# RailDriver.net
KiCad netlist of a schematic drawn in EAGLE
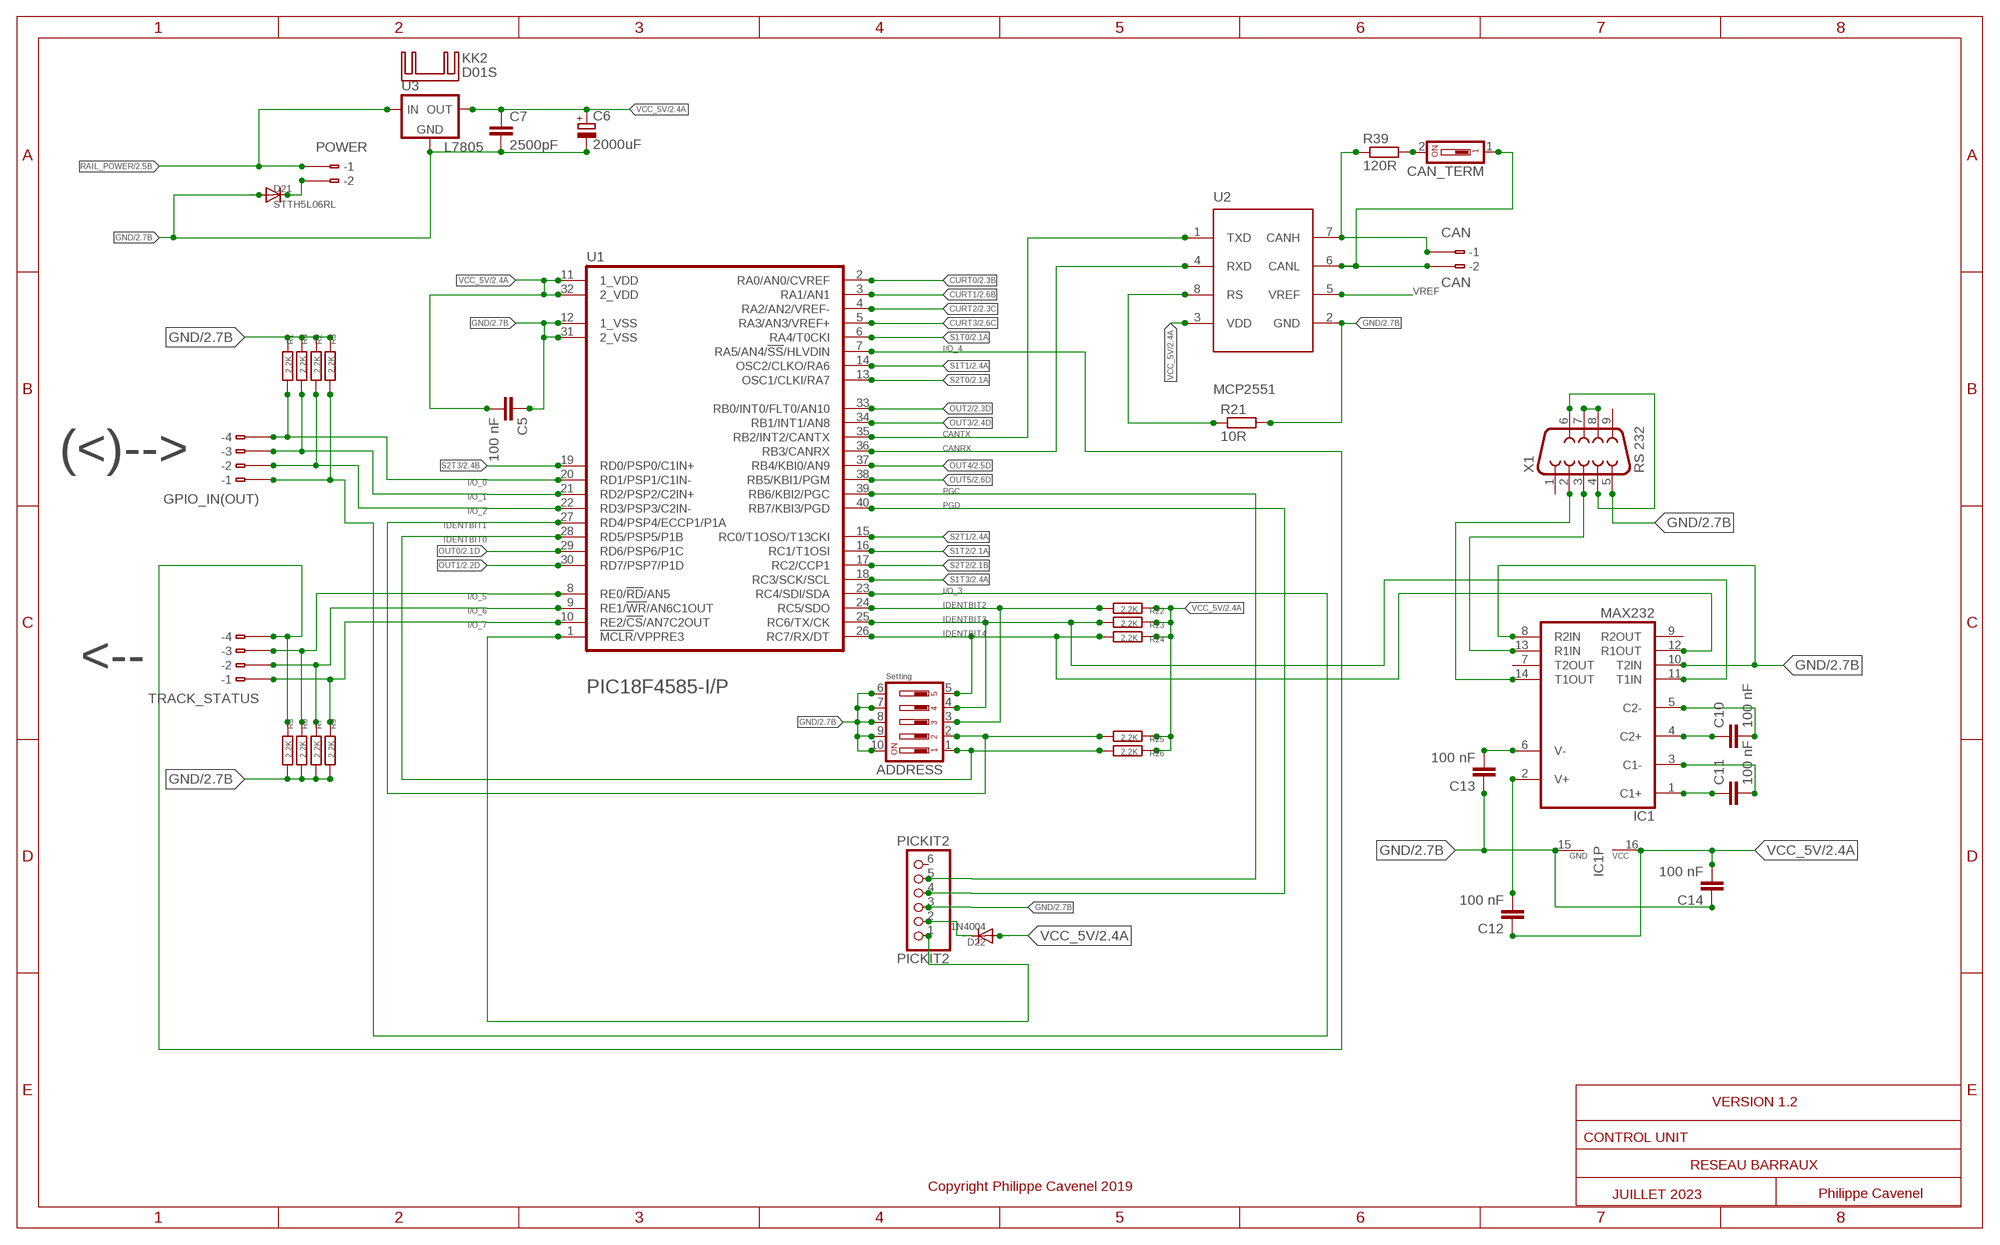
[diagram p0: schematic, sheet 1]
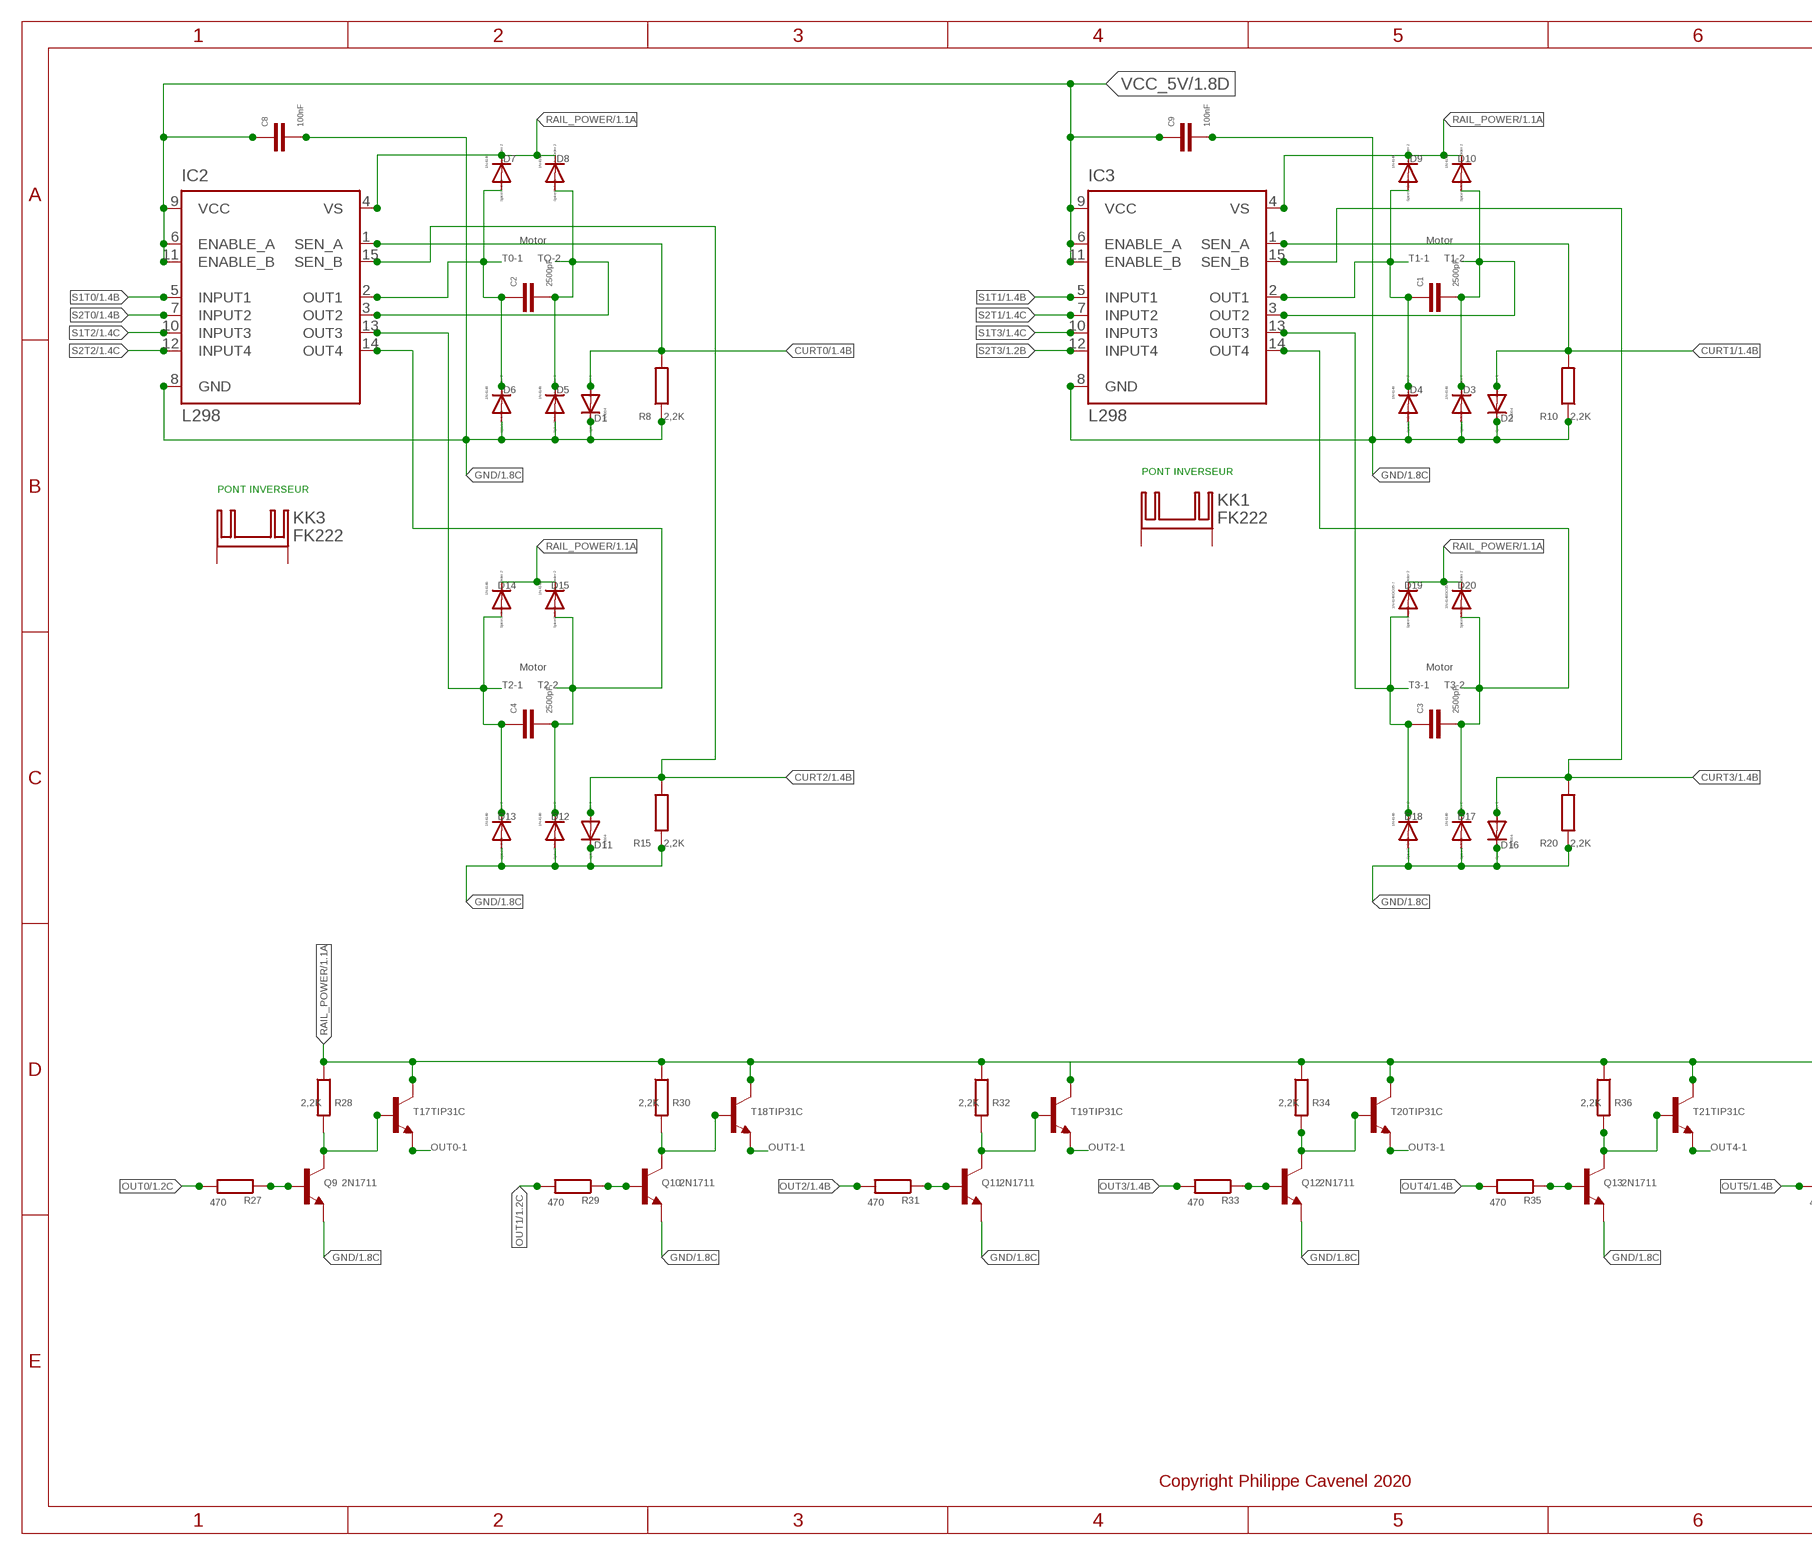
[diagram p1: schematic, sheet 2, part 1 of 2]
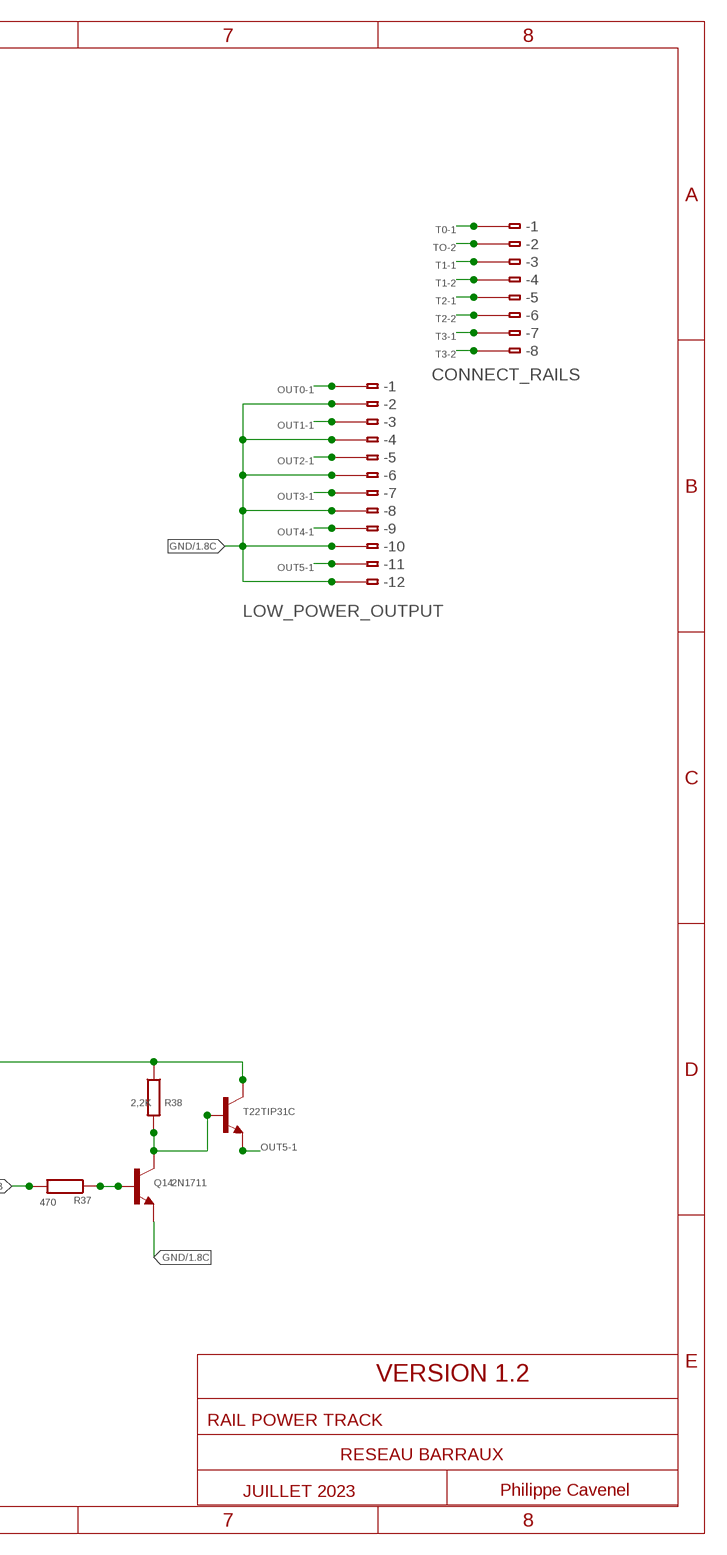
[diagram p2: schematic, sheet 2, part 2 of 2]

(export (version "E")
  (design (tool "Eeschema 10.0.6"))
  (components
    (comp (ref "ADDRESS")
      (value "DIP05YL")
      (footprint "eagle-import:DIP05YL")
      (libsource (lib "eagle-import") (part "DIP05YL"))
    )
    (comp (ref "C5")
      (value "100 nF")
      (footprint "eagle-import:C050-024X044")
      (libsource (lib "eagle-import") (part "C-EU050-024X044"))
    )
    (comp (ref "C6")
      (value "2000uF")
      (footprint "eagle-import:E3,5-10")
      (libsource (lib "eagle-import") (part "CPOL-EUE3.5-10"))
    )
    (comp (ref "C7")
      (value "2500pF")
      (footprint "eagle-import:C050-024X044")
      (libsource (lib "eagle-import") (part "C-EU050-024X044"))
    )
    (comp (ref "C10")
      (value "100 nF")
      (footprint "eagle-import:C050-024X044")
      (libsource (lib "eagle-import") (part "C-EU050-024X044"))
    )
    (comp (ref "C11")
      (value "100 nF")
      (footprint "eagle-import:C050-024X044")
      (libsource (lib "eagle-import") (part "C-EU050-024X044"))
    )
    (comp (ref "C12")
      (value "100 nF")
      (footprint "eagle-import:C050-024X044")
      (libsource (lib "eagle-import") (part "C-EU050-024X044"))
    )
    (comp (ref "C13")
      (value "100 nF")
      (footprint "eagle-import:C050-024X044")
      (libsource (lib "eagle-import") (part "C-EU050-024X044"))
    )
    (comp (ref "C14")
      (value "100 nF")
      (footprint "eagle-import:C050-024X044")
      (libsource (lib "eagle-import") (part "C-EU050-024X044"))
    )
    (comp (ref "CAN")
      (value "CAN")
      (footprint "eagle-import:233-502")
      (fields (field (name "MPN") "233-502"))
      (libsource (lib "eagle-import") (part "233-502"))
    )
    (comp (ref "CAN_TERM")
      (value "DS01")
      (footprint "eagle-import:DS-01")
      (libsource (lib "eagle-import") (part "DS01"))
    )
    (comp (ref "D21")
      (value "STTH5L06RL")
      (footprint "eagle-import:DO201-15")
      (libsource (lib "eagle-import") (part "1N5400"))
    )
    (comp (ref "D22")
      (value "1N4004")
      (footprint "eagle-import:DO41-10")
      (libsource (lib "eagle-import") (part "1N4004"))
    )
    (comp (ref "GPIO_IN(OUT)")
      (value "233-504")
      (footprint "eagle-import:233-504")
      (fields (field (name "MF") "Wago Corporation") (field (name "MPN") "0233-0504"))
      (libsource (lib "eagle-import") (part "233-504"))
    )
    (comp (ref "IC1")
      (value "MAX232")
      (footprint "eagle-import:DIL16")
      (fields (field (name "MF") "MAXIM") (field (name "MPN") "MAX232ACPE+"))
      (libsource (lib "eagle-import") (part "MAX232"))
    )
    (comp (ref "KK2")
      (value "D01S")
      (footprint "eagle-import:D01S")
      (libsource (lib "eagle-import") (part "D01S"))
    )
    (comp (ref "PICKIT2")
      (value "PICKIT2")
      (footprint "eagle-import:1X06")
      (libsource (lib "eagle-import") (part "PINHD-1X6"))
    )
    (comp (ref "POWER")
      (value "233-502")
      (footprint "eagle-import:233-502")
      (libsource (lib "eagle-import") (part "233-502"))
    )
    (comp (ref "R1")
      (value "2,2K")
      (footprint "eagle-import:0204_7")
      (libsource (lib "eagle-import") (part "resistor_R-EU_0204/7"))
    )
    (comp (ref "R2")
      (value "2,2K")
      (footprint "eagle-import:0204_7")
      (libsource (lib "eagle-import") (part "resistor_R-EU_0204/7"))
    )
    (comp (ref "R3")
      (value "2,2K")
      (footprint "eagle-import:0204_7")
      (libsource (lib "eagle-import") (part "resistor_R-EU_0204/7"))
    )
    (comp (ref "R4")
      (value "2,2K")
      (footprint "eagle-import:0204_7")
      (libsource (lib "eagle-import") (part "resistor_R-EU_0204/7"))
    )
    (comp (ref "R5")
      (value "2,2K")
      (footprint "eagle-import:0204_7")
      (libsource (lib "eagle-import") (part "resistor_R-EU_0204/7"))
    )
    (comp (ref "R6")
      (value "2,2K")
      (footprint "eagle-import:0204_7")
      (libsource (lib "eagle-import") (part "resistor_R-EU_0204/7"))
    )
    (comp (ref "R7")
      (value "2,2K")
      (footprint "eagle-import:0204_7")
      (libsource (lib "eagle-import") (part "resistor_R-EU_0204/7"))
    )
    (comp (ref "R9")
      (value "2,2K")
      (footprint "eagle-import:0204_7")
      (libsource (lib "eagle-import") (part "resistor_R-EU_0204/7"))
    )
    (comp (ref "R21")
      (value "10R")
      (footprint "eagle-import:0204_7")
      (libsource (lib "eagle-import") (part "resistor_R-EU_0204/7"))
    )
    (comp (ref "R22")
      (value "2,2K")
      (footprint "eagle-import:0204_7")
      (libsource (lib "eagle-import") (part "resistor_R-EU_0204/7"))
    )
    (comp (ref "R23")
      (value "2,2K")
      (footprint "eagle-import:0204_7")
      (libsource (lib "eagle-import") (part "resistor_R-EU_0204/7"))
    )
    (comp (ref "R24")
      (value "2,2K")
      (footprint "eagle-import:0204_7")
      (libsource (lib "eagle-import") (part "resistor_R-EU_0204/7"))
    )
    (comp (ref "R25")
      (value "2,2K")
      (footprint "eagle-import:0204_7")
      (libsource (lib "eagle-import") (part "resistor_R-EU_0204/7"))
    )
    (comp (ref "R26")
      (value "2,2K")
      (footprint "eagle-import:0204_7")
      (libsource (lib "eagle-import") (part "resistor_R-EU_0204/7"))
    )
    (comp (ref "R39")
      (value "120R")
      (footprint "eagle-import:0204_7")
      (libsource (lib "eagle-import") (part "resistor_R-EU_0204/7"))
    )
    (comp (ref "TRACK_STATUS")
      (value "233-504")
      (footprint "eagle-import:233-504")
      (fields (field (name "MF") "Wago Corporation") (field (name "MPN") "0233-0504"))
      (libsource (lib "eagle-import") (part "233-504"))
    )
    (comp (ref "U1")
      (value "PIC18F4585-I")
      (footprint "eagle-import:DIL_SOCKET40W")
      (fields (field (name "MF") "Microchip") (field (name "MPN") "PIC18F4585-I/P"))
      (libsource (lib "eagle-import") (part "MICROCHIP_PIC18F4585-I-PDIL_SOCKET40W"))
    )
    (comp (ref "U2")
      (value "MCP2551")
      (footprint "eagle-import:DIL_SOCKET8")
      (libsource (lib "eagle-import") (part "MCP2551P"))
    )
    (comp (ref "U3")
      (value "L7805")
      (footprint "eagle-import:TO220BV")
      (libsource (lib "eagle-import") (part "78XX-TO220V"))
    )
    (comp (ref "X1")
      (value "RS 232")
      (footprint "eagle-import:F09HP")
      (libsource (lib "eagle-import") (part "F09HP"))
    )
    (comp (ref "C1")
      (value "2500pF")
      (footprint "eagle-import:C050-024X044")
      (libsource (lib "eagle-import") (part "C-EU050-024X044"))
    )
    (comp (ref "C2")
      (value "2500pF")
      (footprint "eagle-import:C050-024X044")
      (libsource (lib "eagle-import") (part "C-EU050-024X044"))
    )
    (comp (ref "C3")
      (value "2500pF")
      (footprint "eagle-import:C050-024X044")
      (libsource (lib "eagle-import") (part "C-EU050-024X044"))
    )
    (comp (ref "C4")
      (value "2500pF")
      (footprint "eagle-import:C050-024X044")
      (libsource (lib "eagle-import") (part "C-EU050-024X044"))
    )
    (comp (ref "C8")
      (value "100nF")
      (footprint "eagle-import:C050-024X044")
      (libsource (lib "eagle-import") (part "C-EU050-024X044"))
    )
    (comp (ref "C9")
      (value "100nF")
      (footprint "eagle-import:C050-024X044")
      (libsource (lib "eagle-import") (part "C-EU050-024X044"))
    )
    (comp (ref "CONNECT_RAILS")
      (value "233-508")
      (footprint "eagle-import:233-508")
      (fields (field (name "MF") "Wago Corporation") (field (name "MPN") "0233-0508"))
      (libsource (lib "eagle-import") (part "233-508"))
    )
    (comp (ref "D1")
      (value "1N4004")
      (footprint "eagle-import:DO41-10")
      (libsource (lib "eagle-import") (part "1N4004"))
    )
    (comp (ref "D2")
      (value "1N4004")
      (footprint "eagle-import:DO41-10")
      (libsource (lib "eagle-import") (part "1N4004"))
    )
    (comp (ref "D3")
      (value "1N4148")
      (footprint "eagle-import:DO35-7")
      (libsource (lib "eagle-import") (part "1N4148DO35-7"))
    )
    (comp (ref "D4")
      (value "1N4148")
      (footprint "eagle-import:DO35-7")
      (libsource (lib "eagle-import") (part "1N4148DO35-7"))
    )
    (comp (ref "D5")
      (value "1N4148")
      (footprint "eagle-import:DO35-7")
      (libsource (lib "eagle-import") (part "1N4148DO35-7"))
    )
    (comp (ref "D6")
      (value "1N4148")
      (footprint "eagle-import:DO35-7")
      (libsource (lib "eagle-import") (part "1N4148DO35-7"))
    )
    (comp (ref "D7")
      (value "1N4148")
      (footprint "eagle-import:DO35-7")
      (libsource (lib "eagle-import") (part "1N4148DO35-7"))
    )
    (comp (ref "D8")
      (value "1N4148")
      (footprint "eagle-import:DO35-7")
      (libsource (lib "eagle-import") (part "1N4148DO35-7"))
    )
    (comp (ref "D9")
      (value "1N4148")
      (footprint "eagle-import:DO35-7")
      (libsource (lib "eagle-import") (part "1N4148DO35-7"))
    )
    (comp (ref "D10")
      (value "1N4148")
      (footprint "eagle-import:DO35-7")
      (libsource (lib "eagle-import") (part "1N4148DO35-7"))
    )
    (comp (ref "D11")
      (value "1N4004")
      (footprint "eagle-import:DO41-10")
      (libsource (lib "eagle-import") (part "1N4004"))
    )
    (comp (ref "D12")
      (value "1N4148")
      (footprint "eagle-import:DO35-7")
      (libsource (lib "eagle-import") (part "1N4148DO35-7"))
    )
    (comp (ref "D13")
      (value "1N4148")
      (footprint "eagle-import:DO35-7")
      (libsource (lib "eagle-import") (part "1N4148DO35-7"))
    )
    (comp (ref "D14")
      (value "1N4148")
      (footprint "eagle-import:DO35-7")
      (libsource (lib "eagle-import") (part "1N4148DO35-7"))
    )
    (comp (ref "D15")
      (value "1N4148")
      (footprint "eagle-import:DO35-7")
      (libsource (lib "eagle-import") (part "1N4148DO35-7"))
    )
    (comp (ref "D16")
      (value "1N4004")
      (footprint "eagle-import:DO41-10")
      (libsource (lib "eagle-import") (part "1N4004"))
    )
    (comp (ref "D17")
      (value "1N4148")
      (footprint "eagle-import:DO35-7")
      (libsource (lib "eagle-import") (part "1N4148DO35-7"))
    )
    (comp (ref "D18")
      (value "1N4148")
      (footprint "eagle-import:DO35-7")
      (libsource (lib "eagle-import") (part "1N4148DO35-7"))
    )
    (comp (ref "D19")
      (value "1N4148DO35-7")
      (footprint "eagle-import:DO35-7")
      (libsource (lib "eagle-import") (part "1N4148DO35-7"))
    )
    (comp (ref "D20")
      (value "1N4148DO35-7")
      (footprint "eagle-import:DO35-7")
      (libsource (lib "eagle-import") (part "1N4148DO35-7"))
    )
    (comp (ref "IC2")
      (value "L298")
      (footprint "eagle-import:MULTIWATT-15")
      (fields (field (name "MPN") "L298N"))
      (libsource (lib "eagle-import") (part "L298"))
    )
    (comp (ref "IC3")
      (value "L298")
      (footprint "eagle-import:MULTIWATT-15")
      (fields (field (name "MPN") "L298N"))
      (libsource (lib "eagle-import") (part "L298"))
    )
    (comp (ref "KK1")
      (value "FK222")
      (footprint "eagle-import:FK222")
      (libsource (lib "eagle-import") (part "FK222"))
    )
    (comp (ref "KK3")
      (value "FK222")
      (footprint "eagle-import:FK222")
      (libsource (lib "eagle-import") (part "FK222"))
    )
    (comp (ref "LOW_POWER_OUTPUT")
      (value "233-512")
      (footprint "eagle-import:233-512")
      (fields (field (name "MF") "Wago Corporation") (field (name "MPN") "0233-0512"))
      (libsource (lib "eagle-import") (part "233-512"))
    )
    (comp (ref "Q9")
      (value "2N1711")
      (footprint "eagle-import:TO39")
      (libsource (lib "eagle-import") (part "2N1711"))
    )
    (comp (ref "Q10")
      (value "2N1711")
      (footprint "eagle-import:TO39")
      (libsource (lib "eagle-import") (part "2N1711"))
    )
    (comp (ref "Q11")
      (value "2N1711")
      (footprint "eagle-import:TO39")
      (libsource (lib "eagle-import") (part "2N1711"))
    )
    (comp (ref "Q12")
      (value "2N1711")
      (footprint "eagle-import:TO39")
      (libsource (lib "eagle-import") (part "2N1711"))
    )
    (comp (ref "Q13")
      (value "2N1711")
      (footprint "eagle-import:TO39")
      (libsource (lib "eagle-import") (part "2N1711"))
    )
    (comp (ref "Q14")
      (value "2N1711")
      (footprint "eagle-import:TO39")
      (libsource (lib "eagle-import") (part "2N1711"))
    )
    (comp (ref "R8")
      (value "2,2K")
      (footprint "eagle-import:0204_7")
      (libsource (lib "eagle-import") (part "R-EU_0204/7"))
    )
    (comp (ref "R10")
      (value "2,2K")
      (footprint "eagle-import:0204_7")
      (libsource (lib "eagle-import") (part "R-EU_0204/7"))
    )
    (comp (ref "R15")
      (value "2,2K")
      (footprint "eagle-import:0204_7")
      (libsource (lib "eagle-import") (part "R-EU_0204/7"))
    )
    (comp (ref "R20")
      (value "2,2K")
      (footprint "eagle-import:0204_7")
      (libsource (lib "eagle-import") (part "R-EU_0204/7"))
    )
    (comp (ref "R27")
      (value "470")
      (footprint "eagle-import:0204_7")
      (libsource (lib "eagle-import") (part "R-EU_0204/7"))
    )
    (comp (ref "R28")
      (value "2,2K")
      (footprint "eagle-import:0204_7")
      (libsource (lib "eagle-import") (part "R-EU_0204/7"))
    )
    (comp (ref "R29")
      (value "470")
      (footprint "eagle-import:0204_7")
      (libsource (lib "eagle-import") (part "R-EU_0204/7"))
    )
    (comp (ref "R30")
      (value "2,2K")
      (footprint "eagle-import:0204_7")
      (libsource (lib "eagle-import") (part "R-EU_0204/7"))
    )
    (comp (ref "R31")
      (value "470")
      (footprint "eagle-import:0204_7")
      (libsource (lib "eagle-import") (part "R-EU_0204/7"))
    )
    (comp (ref "R32")
      (value "2,2K")
      (footprint "eagle-import:0204_7")
      (libsource (lib "eagle-import") (part "R-EU_0204/7"))
    )
    (comp (ref "R33")
      (value "470")
      (footprint "eagle-import:0204_7")
      (libsource (lib "eagle-import") (part "R-EU_0204/7"))
    )
    (comp (ref "R34")
      (value "2,2K")
      (footprint "eagle-import:0204_7")
      (libsource (lib "eagle-import") (part "R-EU_0204/7"))
    )
    (comp (ref "R35")
      (value "470")
      (footprint "eagle-import:0204_7")
      (libsource (lib "eagle-import") (part "R-EU_0204/7"))
    )
    (comp (ref "R36")
      (value "2,2K")
      (footprint "eagle-import:0204_7")
      (libsource (lib "eagle-import") (part "R-EU_0204/7"))
    )
    (comp (ref "R37")
      (value "470")
      (footprint "eagle-import:0204_7")
      (libsource (lib "eagle-import") (part "R-EU_0204/7"))
    )
    (comp (ref "R38")
      (value "2,2K")
      (footprint "eagle-import:0204_7")
      (libsource (lib "eagle-import") (part "R-EU_0204/7"))
    )
    (comp (ref "T17")
      (value "TIP31C")
      (footprint "eagle-import:TO220")
      (libsource (lib "eagle-import") (part "TIP31C"))
    )
    (comp (ref "T18")
      (value "TIP31C")
      (footprint "eagle-import:TO220")
      (libsource (lib "eagle-import") (part "TIP31C"))
    )
    (comp (ref "T19")
      (value "TIP31C")
      (footprint "eagle-import:TO220")
      (libsource (lib "eagle-import") (part "TIP31C"))
    )
    (comp (ref "T20")
      (value "TIP31C")
      (footprint "eagle-import:TO220")
      (libsource (lib "eagle-import") (part "TIP31C"))
    )
    (comp (ref "T21")
      (value "TIP31C")
      (footprint "eagle-import:TO220")
      (libsource (lib "eagle-import") (part "TIP31C"))
    )
    (comp (ref "T22")
      (value "TIP31C")
      (footprint "eagle-import:TO220")
      (libsource (lib "eagle-import") (part "TIP31C"))
    )
  )
  (nets
    (net (code "1") (name "CANRX") (class "Default")
      (node (ref "U1") (pin "36") (pinfunction "RB3/CANRX_36") (pintype "bidirectional"))
      (node (ref "U2") (pin "4") (pinfunction "RXD_4") (pintype "output"))
    )
    (net (code "2") (name "CANTX") (class "Default")
      (node (ref "U1") (pin "35") (pinfunction "RB2/INT2/CANTX_35") (pintype "bidirectional"))
      (node (ref "U2") (pin "1") (pinfunction "TXD_1") (pintype "input"))
    )
    (net (code "3") (name "CURT0") (class "Default")
      (node (ref "D1") (pin "A") (pinfunction "A_A") (pintype "passive"))
      (node (ref "IC2") (pin "1") (pinfunction "SEN_A_1") (pintype "input"))
      (node (ref "R8") (pin "2") (pinfunction "2_2") (pintype "passive"))
      (node (ref "U1") (pin "2") (pinfunction "RA0/AN0/CVREF_2") (pintype "bidirectional"))
    )
    (net (code "4") (name "CURT1") (class "Default")
      (node (ref "D2") (pin "A") (pinfunction "A_A") (pintype "passive"))
      (node (ref "IC3") (pin "1") (pinfunction "SEN_A_1") (pintype "input"))
      (node (ref "R10") (pin "2") (pinfunction "2_2") (pintype "passive"))
      (node (ref "U1") (pin "3") (pinfunction "RA1/AN1_3") (pintype "bidirectional"))
    )
    (net (code "5") (name "CURT2") (class "Default")
      (node (ref "D11") (pin "A") (pinfunction "A_A") (pintype "passive"))
      (node (ref "IC2") (pin "15") (pinfunction "SEN_B_15") (pintype "input"))
      (node (ref "R15") (pin "2") (pinfunction "2_2") (pintype "passive"))
      (node (ref "U1") (pin "4") (pinfunction "RA2/AN2/VREF-_4") (pintype "bidirectional"))
    )
    (net (code "6") (name "CURT3") (class "Default")
      (node (ref "D16") (pin "A") (pinfunction "A_A") (pintype "passive"))
      (node (ref "IC3") (pin "15") (pinfunction "SEN_B_15") (pintype "input"))
      (node (ref "R20") (pin "2") (pinfunction "2_2") (pintype "passive"))
      (node (ref "U1") (pin "5") (pinfunction "RA3/AN3/VREF+_5") (pintype "bidirectional"))
    )
    (net (code "7") (name "GND") (class "Default")
      (node (ref "ADDRESS") (pin "10") (pinfunction "10_10") (pintype "passive"))
      (node (ref "ADDRESS") (pin "6") (pinfunction "6_6") (pintype "passive"))
      (node (ref "ADDRESS") (pin "7") (pinfunction "7_7") (pintype "passive"))
      (node (ref "ADDRESS") (pin "8") (pinfunction "8_8") (pintype "passive"))
      (node (ref "ADDRESS") (pin "9") (pinfunction "9_9") (pintype "passive"))
      (node (ref "C13") (pin "1") (pinfunction "1_1") (pintype "passive"))
      (node (ref "C14") (pin "1") (pinfunction "1_1") (pintype "passive"))
      (node (ref "C5") (pin "1") (pinfunction "1_1") (pintype "passive"))
      (node (ref "C6") (pin "-") (pinfunction "-_-") (pintype "passive"))
      (node (ref "C7") (pin "2") (pinfunction "2_2") (pintype "passive"))
      (node (ref "C8") (pin "2") (pinfunction "2_2") (pintype "passive"))
      (node (ref "C9") (pin "2") (pinfunction "2_2") (pintype "passive"))
      (node (ref "D1") (pin "C") (pinfunction "C_C") (pintype "passive"))
      (node (ref "D11") (pin "C") (pinfunction "C_C") (pintype "passive"))
      (node (ref "D12") (pin "A") (pinfunction "A_A") (pintype "passive"))
      (node (ref "D13") (pin "A") (pinfunction "A_A") (pintype "passive"))
      (node (ref "D16") (pin "C") (pinfunction "C_C") (pintype "passive"))
      (node (ref "D17") (pin "A") (pinfunction "A_A") (pintype "passive"))
      (node (ref "D18") (pin "A") (pinfunction "A_A") (pintype "passive"))
      (node (ref "D2") (pin "C") (pinfunction "C_C") (pintype "passive"))
      (node (ref "D21") (pin "A") (pinfunction "A_A") (pintype "passive"))
      (node (ref "D3") (pin "A") (pinfunction "A_A") (pintype "passive"))
      (node (ref "D4") (pin "A") (pinfunction "A_A") (pintype "passive"))
      (node (ref "D5") (pin "A") (pinfunction "A_A") (pintype "passive"))
      (node (ref "D6") (pin "A") (pinfunction "A_A") (pintype "passive"))
      (node (ref "IC1") (pin "10") (pinfunction "T2IN_10") (pintype "input"))
      (node (ref "IC1") (pin "15") (pinfunction "GND_15") (pintype "power_in"))
      (node (ref "IC1") (pin "8") (pinfunction "R2IN_8") (pintype "input"))
      (node (ref "IC2") (pin "8") (pinfunction "GND_8") (pintype "power_in"))
      (node (ref "IC3") (pin "8") (pinfunction "GND_8") (pintype "power_in"))
      (node (ref "LOW_POWER_OUTPUT") (pin "B10") (pinfunction "B-10_B10") (pintype "passive"))
      (node (ref "LOW_POWER_OUTPUT") (pin "B12") (pinfunction "B-12_B12") (pintype "passive"))
      (node (ref "LOW_POWER_OUTPUT") (pin "B2") (pinfunction "B-2_B2") (pintype "passive"))
      (node (ref "LOW_POWER_OUTPUT") (pin "B4") (pinfunction "B-4_B4") (pintype "passive"))
      (node (ref "LOW_POWER_OUTPUT") (pin "B6") (pinfunction "B-6_B6") (pintype "passive"))
      (node (ref "LOW_POWER_OUTPUT") (pin "B8") (pinfunction "B-8_B8") (pintype "passive"))
      (node (ref "PICKIT2") (pin "3") (pinfunction "3_3") (pintype "passive"))
      (node (ref "Q10") (pin "1") (pinfunction "E_1") (pintype "passive"))
      (node (ref "Q11") (pin "1") (pinfunction "E_1") (pintype "passive"))
      (node (ref "Q12") (pin "1") (pinfunction "E_1") (pintype "passive"))
      (node (ref "Q13") (pin "1") (pinfunction "E_1") (pintype "passive"))
      (node (ref "Q14") (pin "1") (pinfunction "E_1") (pintype "passive"))
      (node (ref "Q9") (pin "1") (pinfunction "E_1") (pintype "passive"))
      (node (ref "R1") (pin "2") (pinfunction "2_2") (pintype "passive"))
      (node (ref "R10") (pin "1") (pinfunction "1_1") (pintype "passive"))
      (node (ref "R15") (pin "1") (pinfunction "1_1") (pintype "passive"))
      (node (ref "R2") (pin "2") (pinfunction "2_2") (pintype "passive"))
      (node (ref "R20") (pin "1") (pinfunction "1_1") (pintype "passive"))
      (node (ref "R21") (pin "2") (pinfunction "2_2") (pintype "passive"))
      (node (ref "R3") (pin "2") (pinfunction "2_2") (pintype "passive"))
      (node (ref "R4") (pin "2") (pinfunction "2_2") (pintype "passive"))
      (node (ref "R5") (pin "1") (pinfunction "1_1") (pintype "passive"))
      (node (ref "R6") (pin "1") (pinfunction "1_1") (pintype "passive"))
      (node (ref "R7") (pin "1") (pinfunction "1_1") (pintype "passive"))
      (node (ref "R8") (pin "1") (pinfunction "1_1") (pintype "passive"))
      (node (ref "R9") (pin "1") (pinfunction "1_1") (pintype "passive"))
      (node (ref "U1") (pin "12") (pinfunction "1_VSS_12") (pintype "power_in"))
      (node (ref "U1") (pin "31") (pinfunction "2_VSS_31") (pintype "power_in"))
      (node (ref "U2") (pin "2") (pinfunction "GND_2") (pintype "power_in"))
      (node (ref "U3") (pin "2") (pinfunction "GND_2") (pintype "power_in"))
      (node (ref "X1") (pin "5") (pinfunction "5_5") (pintype "passive"))
    )
    (net (code "8") (name "IDENTBIT0") (class "Default")
      (node (ref "ADDRESS") (pin "1") (pinfunction "1_1") (pintype "passive"))
      (node (ref "R26") (pin "1") (pinfunction "1_1") (pintype "passive"))
      (node (ref "U1") (pin "28") (pinfunction "RD5/PSP5/P1B_28") (pintype "bidirectional"))
    )
    (net (code "9") (name "IDENTBIT1") (class "Default")
      (node (ref "ADDRESS") (pin "2") (pinfunction "2_2") (pintype "passive"))
      (node (ref "R25") (pin "1") (pinfunction "1_1") (pintype "passive"))
      (node (ref "U1") (pin "27") (pinfunction "RD4/PSP4/ECCP1/P1A_27") (pintype "bidirectional"))
    )
    (net (code "10") (name "IDENTBIT2") (class "Default")
      (node (ref "ADDRESS") (pin "3") (pinfunction "3_3") (pintype "passive"))
      (node (ref "R22") (pin "1") (pinfunction "1_1") (pintype "passive"))
      (node (ref "U1") (pin "24") (pinfunction "RC5/SDO_24") (pintype "bidirectional"))
    )
    (net (code "11") (name "IDENTBIT3") (class "Default")
      (node (ref "ADDRESS") (pin "4") (pinfunction "4_4") (pintype "passive"))
      (node (ref "IC1") (pin "11") (pinfunction "T1IN_11") (pintype "input"))
      (node (ref "R23") (pin "1") (pinfunction "1_1") (pintype "passive"))
      (node (ref "U1") (pin "25") (pinfunction "RC6/TX/CK_25") (pintype "bidirectional"))
    )
    (net (code "12") (name "IDENTBIT4") (class "Default")
      (node (ref "ADDRESS") (pin "5") (pinfunction "5_5") (pintype "passive"))
      (node (ref "IC1") (pin "12") (pinfunction "R1OUT_12") (pintype "output"))
      (node (ref "R24") (pin "1") (pinfunction "1_1") (pintype "passive"))
      (node (ref "U1") (pin "26") (pinfunction "RC7/RX/DT_26") (pintype "bidirectional"))
    )
    (net (code "13") (name "I{slash}O_0") (class "Default")
      (node (ref "GPIO_IN(OUT)") (pin "B4") (pinfunction "B-4_B4") (pintype "passive"))
      (node (ref "R1") (pin "1") (pinfunction "1_1") (pintype "passive"))
      (node (ref "U1") (pin "20") (pinfunction "RD1/PSP1/C1IN-_20") (pintype "bidirectional"))
    )
    (net (code "14") (name "I{slash}O_1") (class "Default")
      (node (ref "GPIO_IN(OUT)") (pin "B3") (pinfunction "B-3_B3") (pintype "passive"))
      (node (ref "R4") (pin "1") (pinfunction "1_1") (pintype "passive"))
      (node (ref "U1") (pin "21") (pinfunction "RD2/PSP2/C2IN+_21") (pintype "bidirectional"))
    )
    (net (code "15") (name "I{slash}O_2") (class "Default")
      (node (ref "GPIO_IN(OUT)") (pin "B2") (pinfunction "B-2_B2") (pintype "passive"))
      (node (ref "R2") (pin "1") (pinfunction "1_1") (pintype "passive"))
      (node (ref "U1") (pin "22") (pinfunction "RD3/PSP3/C2IN-_22") (pintype "bidirectional"))
    )
    (net (code "16") (name "I{slash}O_3") (class "Default")
      (node (ref "GPIO_IN(OUT)") (pin "B1") (pinfunction "B-1_B1") (pintype "passive"))
      (node (ref "R3") (pin "1") (pinfunction "1_1") (pintype "passive"))
      (node (ref "U1") (pin "23") (pinfunction "RC4/SDI/SDA_23") (pintype "bidirectional"))
    )
    (net (code "17") (name "I{slash}O_4") (class "Default")
      (node (ref "R5") (pin "2") (pinfunction "2_2") (pintype "passive"))
      (node (ref "TRACK_STATUS") (pin "B4") (pinfunction "B-4_B4") (pintype "passive"))
      (node (ref "U1") (pin "7") (pinfunction "RA5/AN4/~{SS}/HLVDIN_7") (pintype "bidirectional"))
    )
    (net (code "18") (name "I{slash}O_5") (class "Default")
      (node (ref "R6") (pin "2") (pinfunction "2_2") (pintype "passive"))
      (node (ref "TRACK_STATUS") (pin "B3") (pinfunction "B-3_B3") (pintype "passive"))
      (node (ref "U1") (pin "8") (pinfunction "RE0/~{RD}/AN5_8") (pintype "bidirectional"))
    )
    (net (code "19") (name "I{slash}O_6") (class "Default")
      (node (ref "R7") (pin "2") (pinfunction "2_2") (pintype "passive"))
      (node (ref "TRACK_STATUS") (pin "B2") (pinfunction "B-2_B2") (pintype "passive"))
      (node (ref "U1") (pin "9") (pinfunction "RE1/~{WR}/AN6C1OUT_9") (pintype "bidirectional"))
    )
    (net (code "20") (name "I{slash}O_7") (class "Default")
      (node (ref "R9") (pin "2") (pinfunction "2_2") (pintype "passive"))
      (node (ref "TRACK_STATUS") (pin "B1") (pinfunction "B-1_B1") (pintype "passive"))
      (node (ref "U1") (pin "10") (pinfunction "RE2/~{CS}/AN7C2OUT_10") (pintype "bidirectional"))
    )
    (net (code "21") (name "Net-(CAN-B-1)") (class "Default")
      (node (ref "CAN") (pin "B1") (pinfunction "B-1_B1") (pintype "passive"))
      (node (ref "R39") (pin "1") (pinfunction "1_1") (pintype "passive"))
      (node (ref "U2") (pin "7") (pinfunction "CANH_7") (pintype "bidirectional"))
    )
    (net (code "22") (name "Net-(CAN-B-2)") (class "Default")
      (node (ref "CAN") (pin "B2") (pinfunction "B-2_B2") (pintype "passive"))
      (node (ref "CAN_TERM") (pin "1") (pinfunction "1_1") (pintype "passive"))
      (node (ref "U2") (pin "6") (pinfunction "CANL_6") (pintype "bidirectional"))
    )
    (net (code "23") (name "Net-(CAN_TERM-Pad2)") (class "Default")
      (node (ref "CAN_TERM") (pin "2") (pinfunction "2_2") (pintype "passive"))
      (node (ref "R39") (pin "2") (pinfunction "2_2") (pintype "passive"))
    )
    (net (code "24") (name "Net-(D22-PadC)") (class "Default")
      (node (ref "D22") (pin "C") (pinfunction "C_C") (pintype "passive"))
      (node (ref "PICKIT2") (pin "2") (pinfunction "2_2") (pintype "passive"))
    )
    (net (code "25") (name "Net-(IC1A-C1+)") (class "Default")
      (node (ref "C11") (pin "1") (pinfunction "1_1") (pintype "passive"))
      (node (ref "IC1") (pin "1") (pinfunction "C1+_1") (pintype "bidirectional"))
    )
    (net (code "26") (name "Net-(IC1A-C1-)") (class "Default")
      (node (ref "C11") (pin "2") (pinfunction "2_2") (pintype "passive"))
      (node (ref "IC1") (pin "3") (pinfunction "C1-_3") (pintype "bidirectional"))
    )
    (net (code "27") (name "Net-(IC1A-C2+)") (class "Default")
      (node (ref "C10") (pin "1") (pinfunction "1_1") (pintype "passive"))
      (node (ref "IC1") (pin "4") (pinfunction "C2+_4") (pintype "bidirectional"))
    )
    (net (code "28") (name "Net-(IC1A-C2-)") (class "Default")
      (node (ref "C10") (pin "2") (pinfunction "2_2") (pintype "passive"))
      (node (ref "IC1") (pin "5") (pinfunction "C2-_5") (pintype "bidirectional"))
    )
    (net (code "29") (name "Net-(IC1A-R1IN)") (class "Default")
      (node (ref "IC1") (pin "13") (pinfunction "R1IN_13") (pintype "input"))
      (node (ref "X1") (pin "3") (pinfunction "3_3") (pintype "passive"))
    )
    (net (code "30") (name "Net-(IC1A-T1OUT)") (class "Default")
      (node (ref "IC1") (pin "14") (pinfunction "T1OUT_14") (pintype "output"))
      (node (ref "X1") (pin "2") (pinfunction "2_2") (pintype "passive"))
    )
    (net (code "31") (name "Net-(IC1A-V+)") (class "Default")
      (node (ref "C12") (pin "2") (pinfunction "2_2") (pintype "passive"))
      (node (ref "IC1") (pin "2") (pinfunction "V+_2") (pintype "bidirectional"))
    )
    (net (code "32") (name "Net-(IC1A-V-)") (class "Default")
      (node (ref "C13") (pin "2") (pinfunction "2_2") (pintype "passive"))
      (node (ref "IC1") (pin "6") (pinfunction "V-_6") (pintype "bidirectional"))
    )
    (net (code "33") (name "Net-(POWER-B-2)") (class "Default")
      (node (ref "D21") (pin "C") (pinfunction "C_C") (pintype "passive"))
      (node (ref "POWER") (pin "B2") (pinfunction "B-2_B2") (pintype "passive"))
    )
    (net (code "34") (name "Net-(Q9-B)") (class "Default")
      (node (ref "Q9") (pin "2") (pinfunction "B_2") (pintype "passive"))
      (node (ref "R27") (pin "1") (pinfunction "1_1") (pintype "passive"))
    )
    (net (code "35") (name "Net-(Q9-C)") (class "Default")
      (node (ref "Q9") (pin "3") (pinfunction "C_3") (pintype "passive"))
      (node (ref "R28") (pin "2") (pinfunction "2_2") (pintype "passive"))
      (node (ref "T17") (pin "1") (pinfunction "B_1") (pintype "passive"))
    )
    (net (code "36") (name "Net-(Q10-B)") (class "Default")
      (node (ref "Q10") (pin "2") (pinfunction "B_2") (pintype "passive"))
      (node (ref "R29") (pin "1") (pinfunction "1_1") (pintype "passive"))
    )
    (net (code "37") (name "Net-(Q10-C)") (class "Default")
      (node (ref "Q10") (pin "3") (pinfunction "C_3") (pintype "passive"))
      (node (ref "R30") (pin "2") (pinfunction "2_2") (pintype "passive"))
      (node (ref "T18") (pin "1") (pinfunction "B_1") (pintype "passive"))
    )
    (net (code "38") (name "Net-(Q11-B)") (class "Default")
      (node (ref "Q11") (pin "2") (pinfunction "B_2") (pintype "passive"))
      (node (ref "R31") (pin "1") (pinfunction "1_1") (pintype "passive"))
    )
    (net (code "39") (name "Net-(Q11-C)") (class "Default")
      (node (ref "Q11") (pin "3") (pinfunction "C_3") (pintype "passive"))
      (node (ref "R32") (pin "2") (pinfunction "2_2") (pintype "passive"))
      (node (ref "T19") (pin "1") (pinfunction "B_1") (pintype "passive"))
    )
    (net (code "40") (name "Net-(Q12-B)") (class "Default")
      (node (ref "Q12") (pin "2") (pinfunction "B_2") (pintype "passive"))
      (node (ref "R33") (pin "1") (pinfunction "1_1") (pintype "passive"))
    )
    (net (code "41") (name "Net-(Q12-C)") (class "Default")
      (node (ref "Q12") (pin "3") (pinfunction "C_3") (pintype "passive"))
      (node (ref "R34") (pin "2") (pinfunction "2_2") (pintype "passive"))
      (node (ref "T20") (pin "1") (pinfunction "B_1") (pintype "passive"))
    )
    (net (code "42") (name "Net-(Q13-B)") (class "Default")
      (node (ref "Q13") (pin "2") (pinfunction "B_2") (pintype "passive"))
      (node (ref "R35") (pin "1") (pinfunction "1_1") (pintype "passive"))
    )
    (net (code "43") (name "Net-(Q13-C)") (class "Default")
      (node (ref "Q13") (pin "3") (pinfunction "C_3") (pintype "passive"))
      (node (ref "R36") (pin "2") (pinfunction "2_2") (pintype "passive"))
      (node (ref "T21") (pin "1") (pinfunction "B_1") (pintype "passive"))
    )
    (net (code "44") (name "Net-(Q14-B)") (class "Default")
      (node (ref "Q14") (pin "2") (pinfunction "B_2") (pintype "passive"))
      (node (ref "R37") (pin "1") (pinfunction "1_1") (pintype "passive"))
    )
    (net (code "45") (name "Net-(Q14-C)") (class "Default")
      (node (ref "Q14") (pin "3") (pinfunction "C_3") (pintype "passive"))
      (node (ref "R38") (pin "2") (pinfunction "2_2") (pintype "passive"))
      (node (ref "T22") (pin "1") (pinfunction "B_1") (pintype "passive"))
    )
    (net (code "46") (name "Net-(U1-~{MCLR}{slash}VPPRE3)") (class "Default")
      (node (ref "PICKIT2") (pin "1") (pinfunction "1_1") (pintype "passive"))
      (node (ref "U1") (pin "1") (pinfunction "~{MCLR}/VPPRE3_1") (pintype "input"))
    )
    (net (code "47") (name "Net-(U2-RS)") (class "Default")
      (node (ref "R21") (pin "1") (pinfunction "1_1") (pintype "passive"))
      (node (ref "U2") (pin "8") (pinfunction "RS_8") (pintype "input"))
    )
    (net (code "48") (name "Net-(X1-Pad4)") (class "Default")
      (node (ref "X1") (pin "4") (pinfunction "4_4") (pintype "passive"))
      (node (ref "X1") (pin "6") (pinfunction "6_6") (pintype "passive"))
    )
    (net (code "49") (name "Net-(X1-Pad7)") (class "Default")
      (node (ref "X1") (pin "7") (pinfunction "7_7") (pintype "passive"))
      (node (ref "X1") (pin "8") (pinfunction "8_8") (pintype "passive"))
    )
    (net (code "50") (name "OUT0") (class "Default")
      (node (ref "R27") (pin "2") (pinfunction "2_2") (pintype "passive"))
      (node (ref "U1") (pin "29") (pinfunction "RD6/PSP6/P1C_29") (pintype "bidirectional"))
    )
    (net (code "51") (name "OUT0-1") (class "Default")
      (node (ref "LOW_POWER_OUTPUT") (pin "B1") (pinfunction "B-1_B1") (pintype "passive"))
      (node (ref "T17") (pin "3") (pinfunction "E_3") (pintype "passive"))
    )
    (net (code "52") (name "OUT1") (class "Default")
      (node (ref "R29") (pin "2") (pinfunction "2_2") (pintype "passive"))
      (node (ref "U1") (pin "30") (pinfunction "RD7/PSP7/P1D_30") (pintype "bidirectional"))
    )
    (net (code "53") (name "OUT1-1") (class "Default")
      (node (ref "LOW_POWER_OUTPUT") (pin "B3") (pinfunction "B-3_B3") (pintype "passive"))
      (node (ref "T18") (pin "3") (pinfunction "E_3") (pintype "passive"))
    )
    (net (code "54") (name "OUT2") (class "Default")
      (node (ref "R31") (pin "2") (pinfunction "2_2") (pintype "passive"))
      (node (ref "U1") (pin "33") (pinfunction "RB0/INT0/FLT0/AN10_33") (pintype "bidirectional"))
    )
    (net (code "55") (name "OUT2-1") (class "Default")
      (node (ref "LOW_POWER_OUTPUT") (pin "B5") (pinfunction "B-5_B5") (pintype "passive"))
      (node (ref "T19") (pin "3") (pinfunction "E_3") (pintype "passive"))
    )
    (net (code "56") (name "OUT3") (class "Default")
      (node (ref "R33") (pin "2") (pinfunction "2_2") (pintype "passive"))
      (node (ref "U1") (pin "34") (pinfunction "RB1/INT1/AN8_34") (pintype "bidirectional"))
    )
    (net (code "57") (name "OUT3-1") (class "Default")
      (node (ref "LOW_POWER_OUTPUT") (pin "B7") (pinfunction "B-7_B7") (pintype "passive"))
      (node (ref "T20") (pin "3") (pinfunction "E_3") (pintype "passive"))
    )
    (net (code "58") (name "OUT4") (class "Default")
      (node (ref "R35") (pin "2") (pinfunction "2_2") (pintype "passive"))
      (node (ref "U1") (pin "37") (pinfunction "RB4/KBI0/AN9_37") (pintype "bidirectional"))
    )
    (net (code "59") (name "OUT4-1") (class "Default")
      (node (ref "LOW_POWER_OUTPUT") (pin "B9") (pinfunction "B-9_B9") (pintype "passive"))
      (node (ref "T21") (pin "3") (pinfunction "E_3") (pintype "passive"))
    )
    (net (code "60") (name "OUT5") (class "Default")
      (node (ref "R37") (pin "2") (pinfunction "2_2") (pintype "passive"))
      (node (ref "U1") (pin "38") (pinfunction "RB5/KBI1/PGM_38") (pintype "bidirectional"))
    )
    (net (code "61") (name "OUT5-1") (class "Default")
      (node (ref "LOW_POWER_OUTPUT") (pin "B11") (pinfunction "B-11_B11") (pintype "passive"))
      (node (ref "T22") (pin "3") (pinfunction "E_3") (pintype "passive"))
    )
    (net (code "62") (name "PGC") (class "Default")
      (node (ref "PICKIT2") (pin "5") (pinfunction "5_5") (pintype "passive"))
      (node (ref "U1") (pin "39") (pinfunction "RB6/KBI2/PGC_39") (pintype "bidirectional"))
    )
    (net (code "63") (name "PGD") (class "Default")
      (node (ref "PICKIT2") (pin "4") (pinfunction "4_4") (pintype "passive"))
      (node (ref "U1") (pin "40") (pinfunction "RB7/KBI3/PGD_40") (pintype "bidirectional"))
    )
    (net (code "64") (name "RAIL_POWER") (class "Default")
      (node (ref "D10") (pin "C") (pinfunction "C_C") (pintype "passive"))
      (node (ref "D14") (pin "C") (pinfunction "C_C") (pintype "passive"))
      (node (ref "D15") (pin "C") (pinfunction "C_C") (pintype "passive"))
      (node (ref "D19") (pin "C") (pinfunction "C_C") (pintype "passive"))
      (node (ref "D20") (pin "C") (pinfunction "C_C") (pintype "passive"))
      (node (ref "D7") (pin "C") (pinfunction "C_C") (pintype "passive"))
      (node (ref "D8") (pin "C") (pinfunction "C_C") (pintype "passive"))
      (node (ref "D9") (pin "C") (pinfunction "C_C") (pintype "passive"))
      (node (ref "IC2") (pin "4") (pinfunction "VS_4") (pintype "power_in"))
      (node (ref "IC3") (pin "4") (pinfunction "VS_4") (pintype "power_in"))
      (node (ref "POWER") (pin "B1") (pinfunction "B-1_B1") (pintype "passive"))
      (node (ref "R28") (pin "1") (pinfunction "1_1") (pintype "passive"))
      (node (ref "R30") (pin "1") (pinfunction "1_1") (pintype "passive"))
      (node (ref "R32") (pin "1") (pinfunction "1_1") (pintype "passive"))
      (node (ref "R34") (pin "1") (pinfunction "1_1") (pintype "passive"))
      (node (ref "R36") (pin "1") (pinfunction "1_1") (pintype "passive"))
      (node (ref "R38") (pin "1") (pinfunction "1_1") (pintype "passive"))
      (node (ref "T17") (pin "2") (pinfunction "C_2") (pintype "passive"))
      (node (ref "T18") (pin "2") (pinfunction "C_2") (pintype "passive"))
      (node (ref "T19") (pin "2") (pinfunction "C_2") (pintype "passive"))
      (node (ref "T20") (pin "2") (pinfunction "C_2") (pintype "passive"))
      (node (ref "T21") (pin "2") (pinfunction "C_2") (pintype "passive"))
      (node (ref "T22") (pin "2") (pinfunction "C_2") (pintype "passive"))
      (node (ref "U3") (pin "1") (pinfunction "VIN_1") (pintype "power_in"))
    )
    (net (code "65") (name "S1T0") (class "Default")
      (node (ref "IC2") (pin "5") (pinfunction "INPUT1_5") (pintype "input"))
      (node (ref "U1") (pin "6") (pinfunction "RA4/T0CKI_6") (pintype "bidirectional"))
    )
    (net (code "66") (name "S1T1") (class "Default")
      (node (ref "IC3") (pin "5") (pinfunction "INPUT1_5") (pintype "input"))
      (node (ref "U1") (pin "14") (pinfunction "OSC2/CLKO/RA6_14") (pintype "bidirectional"))
    )
    (net (code "67") (name "S1T2") (class "Default")
      (node (ref "IC2") (pin "10") (pinfunction "INPUT3_10") (pintype "input"))
      (node (ref "U1") (pin "16") (pinfunction "RC1/T1OSI_16") (pintype "bidirectional"))
    )
    (net (code "68") (name "S1T3") (class "Default")
      (node (ref "IC3") (pin "10") (pinfunction "INPUT3_10") (pintype "input"))
      (node (ref "U1") (pin "18") (pinfunction "RC3/SCK/SCL_18") (pintype "bidirectional"))
    )
    (net (code "69") (name "S2T0") (class "Default")
      (node (ref "IC2") (pin "7") (pinfunction "INPUT2_7") (pintype "input"))
      (node (ref "U1") (pin "13") (pinfunction "OSC1/CLKI/RA7_13") (pintype "bidirectional"))
    )
    (net (code "70") (name "S2T1") (class "Default")
      (node (ref "IC3") (pin "7") (pinfunction "INPUT2_7") (pintype "input"))
      (node (ref "U1") (pin "15") (pinfunction "RC0/T1OSO/T13CKI_15") (pintype "bidirectional"))
    )
    (net (code "71") (name "S2T2") (class "Default")
      (node (ref "IC2") (pin "12") (pinfunction "INPUT4_12") (pintype "input"))
      (node (ref "U1") (pin "17") (pinfunction "RC2/CCP1_17") (pintype "bidirectional"))
    )
    (net (code "72") (name "S2T3") (class "Default")
      (node (ref "IC3") (pin "12") (pinfunction "INPUT4_12") (pintype "input"))
      (node (ref "U1") (pin "19") (pinfunction "RD0/PSP0/C1IN+_19") (pintype "bidirectional"))
    )
    (net (code "73") (name "T0-1") (class "Default")
      (node (ref "C2") (pin "1") (pinfunction "1_1") (pintype "passive"))
      (node (ref "CONNECT_RAILS") (pin "B1") (pinfunction "B-1_B1") (pintype "passive"))
      (node (ref "D6") (pin "C") (pinfunction "C_C") (pintype "passive"))
      (node (ref "D7") (pin "A") (pinfunction "A_A") (pintype "passive"))
      (node (ref "IC2") (pin "2") (pinfunction "OUT1_2") (pintype "output"))
    )
    (net (code "74") (name "T1-1") (class "Default")
      (node (ref "C1") (pin "1") (pinfunction "1_1") (pintype "passive"))
      (node (ref "CONNECT_RAILS") (pin "B3") (pinfunction "B-3_B3") (pintype "passive"))
      (node (ref "D4") (pin "C") (pinfunction "C_C") (pintype "passive"))
      (node (ref "D9") (pin "A") (pinfunction "A_A") (pintype "passive"))
      (node (ref "IC3") (pin "2") (pinfunction "OUT1_2") (pintype "output"))
    )
    (net (code "75") (name "T1-2") (class "Default")
      (node (ref "C1") (pin "2") (pinfunction "2_2") (pintype "passive"))
      (node (ref "CONNECT_RAILS") (pin "B4") (pinfunction "B-4_B4") (pintype "passive"))
      (node (ref "D10") (pin "A") (pinfunction "A_A") (pintype "passive"))
      (node (ref "D3") (pin "C") (pinfunction "C_C") (pintype "passive"))
      (node (ref "IC3") (pin "3") (pinfunction "OUT2_3") (pintype "output"))
    )
    (net (code "76") (name "T2-1") (class "Default")
      (node (ref "C4") (pin "1") (pinfunction "1_1") (pintype "passive"))
      (node (ref "CONNECT_RAILS") (pin "B5") (pinfunction "B-5_B5") (pintype "passive"))
      (node (ref "D13") (pin "C") (pinfunction "C_C") (pintype "passive"))
      (node (ref "D14") (pin "A") (pinfunction "A_A") (pintype "passive"))
      (node (ref "IC2") (pin "13") (pinfunction "OUT3_13") (pintype "output"))
    )
    (net (code "77") (name "T2-2") (class "Default")
      (node (ref "C4") (pin "2") (pinfunction "2_2") (pintype "passive"))
      (node (ref "CONNECT_RAILS") (pin "B6") (pinfunction "B-6_B6") (pintype "passive"))
      (node (ref "D12") (pin "C") (pinfunction "C_C") (pintype "passive"))
      (node (ref "D15") (pin "A") (pinfunction "A_A") (pintype "passive"))
      (node (ref "IC2") (pin "14") (pinfunction "OUT4_14") (pintype "output"))
    )
    (net (code "78") (name "T3-1") (class "Default")
      (node (ref "C3") (pin "1") (pinfunction "1_1") (pintype "passive"))
      (node (ref "CONNECT_RAILS") (pin "B7") (pinfunction "B-7_B7") (pintype "passive"))
      (node (ref "D18") (pin "C") (pinfunction "C_C") (pintype "passive"))
      (node (ref "D19") (pin "A") (pinfunction "A_A") (pintype "passive"))
      (node (ref "IC3") (pin "13") (pinfunction "OUT3_13") (pintype "output"))
    )
    (net (code "79") (name "T3-2") (class "Default")
      (node (ref "C3") (pin "2") (pinfunction "2_2") (pintype "passive"))
      (node (ref "CONNECT_RAILS") (pin "B8") (pinfunction "B-8_B8") (pintype "passive"))
      (node (ref "D17") (pin "C") (pinfunction "C_C") (pintype "passive"))
      (node (ref "D20") (pin "A") (pinfunction "A_A") (pintype "passive"))
      (node (ref "IC3") (pin "14") (pinfunction "OUT4_14") (pintype "output"))
    )
    (net (code "80") (name "TO-2") (class "Default")
      (node (ref "C2") (pin "2") (pinfunction "2_2") (pintype "passive"))
      (node (ref "CONNECT_RAILS") (pin "B2") (pinfunction "B-2_B2") (pintype "passive"))
      (node (ref "D5") (pin "C") (pinfunction "C_C") (pintype "passive"))
      (node (ref "D8") (pin "A") (pinfunction "A_A") (pintype "passive"))
      (node (ref "IC2") (pin "3") (pinfunction "OUT2_3") (pintype "output"))
    )
    (net (code "81") (name "VCC_5V") (class "Default")
      (node (ref "C12") (pin "1") (pinfunction "1_1") (pintype "passive"))
      (node (ref "C14") (pin "2") (pinfunction "2_2") (pintype "passive"))
      (node (ref "C5") (pin "2") (pinfunction "2_2") (pintype "passive"))
      (node (ref "C6") (pin "+") (pinfunction "+_+") (pintype "passive"))
      (node (ref "C7") (pin "1") (pinfunction "1_1") (pintype "passive"))
      (node (ref "C8") (pin "1") (pinfunction "1_1") (pintype "passive"))
      (node (ref "C9") (pin "1") (pinfunction "1_1") (pintype "passive"))
      (node (ref "D22") (pin "A") (pinfunction "A_A") (pintype "passive"))
      (node (ref "IC1") (pin "16") (pinfunction "VCC_16") (pintype "power_in"))
      (node (ref "IC2") (pin "11") (pinfunction "ENABLE_B_11") (pintype "input"))
      (node (ref "IC2") (pin "6") (pinfunction "ENABLE_A_6") (pintype "input"))
      (node (ref "IC2") (pin "9") (pinfunction "VCC_9") (pintype "power_in"))
      (node (ref "IC3") (pin "11") (pinfunction "ENABLE_B_11") (pintype "input"))
      (node (ref "IC3") (pin "6") (pinfunction "ENABLE_A_6") (pintype "input"))
      (node (ref "IC3") (pin "9") (pinfunction "VCC_9") (pintype "power_in"))
      (node (ref "R22") (pin "2") (pinfunction "2_2") (pintype "passive"))
      (node (ref "R23") (pin "2") (pinfunction "2_2") (pintype "passive"))
      (node (ref "R24") (pin "2") (pinfunction "2_2") (pintype "passive"))
      (node (ref "R25") (pin "2") (pinfunction "2_2") (pintype "passive"))
      (node (ref "R26") (pin "2") (pinfunction "2_2") (pintype "passive"))
      (node (ref "U1") (pin "11") (pinfunction "1_VDD_11") (pintype "power_in"))
      (node (ref "U1") (pin "32") (pinfunction "2_VDD_32") (pintype "power_in"))
      (node (ref "U2") (pin "3") (pinfunction "VDD_3") (pintype "input"))
      (node (ref "U3") (pin "3") (pinfunction "VOUT_3") (pintype "power_in"))
    )
    (net (code "82") (name "VREF") (class "Default")
      (node (ref "U2") (pin "5") (pinfunction "VREF_5") (pintype "power_in"))
    )
    (net (code "83") (name "unconnected-(CAN--1-PadA1)") (class "Default")
      (node (ref "CAN") (pin "A1") (pinfunction "-1_A1") (pintype "passive"))
    )
    (net (code "84") (name "unconnected-(CAN--2-PadA2)") (class "Default")
      (node (ref "CAN") (pin "A2") (pinfunction "-2_A2") (pintype "passive"))
    )
    (net (code "85") (name "unconnected-(CONNECT_RAILS--1-PadA1)") (class "Default")
      (node (ref "CONNECT_RAILS") (pin "A1") (pinfunction "-1_A1") (pintype "passive"))
    )
    (net (code "86") (name "unconnected-(CONNECT_RAILS--2-PadA2)") (class "Default")
      (node (ref "CONNECT_RAILS") (pin "A2") (pinfunction "-2_A2") (pintype "passive"))
    )
    (net (code "87") (name "unconnected-(CONNECT_RAILS--3-PadA3)") (class "Default")
      (node (ref "CONNECT_RAILS") (pin "A3") (pinfunction "-3_A3") (pintype "passive"))
    )
    (net (code "88") (name "unconnected-(CONNECT_RAILS--4-PadA4)") (class "Default")
      (node (ref "CONNECT_RAILS") (pin "A4") (pinfunction "-4_A4") (pintype "passive"))
    )
    (net (code "89") (name "unconnected-(CONNECT_RAILS--5-PadA5)") (class "Default")
      (node (ref "CONNECT_RAILS") (pin "A5") (pinfunction "-5_A5") (pintype "passive"))
    )
    (net (code "90") (name "unconnected-(CONNECT_RAILS--6-PadA6)") (class "Default")
      (node (ref "CONNECT_RAILS") (pin "A6") (pinfunction "-6_A6") (pintype "passive"))
    )
    (net (code "91") (name "unconnected-(CONNECT_RAILS--7-PadA7)") (class "Default")
      (node (ref "CONNECT_RAILS") (pin "A7") (pinfunction "-7_A7") (pintype "passive"))
    )
    (net (code "92") (name "unconnected-(CONNECT_RAILS--8-PadA8)") (class "Default")
      (node (ref "CONNECT_RAILS") (pin "A8") (pinfunction "-8_A8") (pintype "passive"))
    )
    (net (code "93") (name "unconnected-(GPIO_IN(OUT)--1-PadA1)") (class "Default")
      (node (ref "GPIO_IN(OUT)") (pin "A1") (pinfunction "-1_A1") (pintype "passive"))
    )
    (net (code "94") (name "unconnected-(GPIO_IN(OUT)--2-PadA2)") (class "Default")
      (node (ref "GPIO_IN(OUT)") (pin "A2") (pinfunction "-2_A2") (pintype "passive"))
    )
    (net (code "95") (name "unconnected-(GPIO_IN(OUT)--3-PadA3)") (class "Default")
      (node (ref "GPIO_IN(OUT)") (pin "A3") (pinfunction "-3_A3") (pintype "passive"))
    )
    (net (code "96") (name "unconnected-(GPIO_IN(OUT)--4-PadA4)") (class "Default")
      (node (ref "GPIO_IN(OUT)") (pin "A4") (pinfunction "-4_A4") (pintype "passive"))
    )
    (net (code "97") (name "unconnected-(IC1A-R2OUT-Pad9)") (class "Default")
      (node (ref "IC1") (pin "9") (pinfunction "R2OUT_9") (pintype "output"))
    )
    (net (code "98") (name "unconnected-(IC1A-T2OUT-Pad7)") (class "Default")
      (node (ref "IC1") (pin "7") (pinfunction "T2OUT_7") (pintype "output"))
    )
    (net (code "99") (name "unconnected-(KK1-K-PadA2,8)") (class "Default")
      (node (ref "KK1") (pin "A2,8") (pinfunction "K_A2,8") (pintype "passive"))
    )
    (net (code "100") (name "unconnected-(KK1-K-PadB2,8)") (class "Default")
      (node (ref "KK1") (pin "B2,8") (pinfunction "K_B2,8") (pintype "passive"))
    )
    (net (code "101") (name "unconnected-(KK3-K-PadA2,8)") (class "Default")
      (node (ref "KK3") (pin "A2,8") (pinfunction "K_A2,8") (pintype "passive"))
    )
    (net (code "102") (name "unconnected-(KK3-K-PadB2,8)") (class "Default")
      (node (ref "KK3") (pin "B2,8") (pinfunction "K_B2,8") (pintype "passive"))
    )
    (net (code "103") (name "unconnected-(LOW_POWER_OUTPUT--1-PadA1)") (class "Default")
      (node (ref "LOW_POWER_OUTPUT") (pin "A1") (pinfunction "-1_A1") (pintype "passive"))
    )
    (net (code "104") (name "unconnected-(LOW_POWER_OUTPUT--2-PadA2)") (class "Default")
      (node (ref "LOW_POWER_OUTPUT") (pin "A2") (pinfunction "-2_A2") (pintype "passive"))
    )
    (net (code "105") (name "unconnected-(LOW_POWER_OUTPUT--3-PadA3)") (class "Default")
      (node (ref "LOW_POWER_OUTPUT") (pin "A3") (pinfunction "-3_A3") (pintype "passive"))
    )
    (net (code "106") (name "unconnected-(LOW_POWER_OUTPUT--4-PadA4)") (class "Default")
      (node (ref "LOW_POWER_OUTPUT") (pin "A4") (pinfunction "-4_A4") (pintype "passive"))
    )
    (net (code "107") (name "unconnected-(LOW_POWER_OUTPUT--5-PadA5)") (class "Default")
      (node (ref "LOW_POWER_OUTPUT") (pin "A5") (pinfunction "-5_A5") (pintype "passive"))
    )
    (net (code "108") (name "unconnected-(LOW_POWER_OUTPUT--6-PadA6)") (class "Default")
      (node (ref "LOW_POWER_OUTPUT") (pin "A6") (pinfunction "-6_A6") (pintype "passive"))
    )
    (net (code "109") (name "unconnected-(LOW_POWER_OUTPUT--7-PadA7)") (class "Default")
      (node (ref "LOW_POWER_OUTPUT") (pin "A7") (pinfunction "-7_A7") (pintype "passive"))
    )
    (net (code "110") (name "unconnected-(LOW_POWER_OUTPUT--8-PadA8)") (class "Default")
      (node (ref "LOW_POWER_OUTPUT") (pin "A8") (pinfunction "-8_A8") (pintype "passive"))
    )
    (net (code "111") (name "unconnected-(LOW_POWER_OUTPUT--9-PadA9)") (class "Default")
      (node (ref "LOW_POWER_OUTPUT") (pin "A9") (pinfunction "-9_A9") (pintype "passive"))
    )
    (net (code "112") (name "unconnected-(LOW_POWER_OUTPUT--10-PadA10)") (class "Default")
      (node (ref "LOW_POWER_OUTPUT") (pin "A10") (pinfunction "-10_A10") (pintype "passive"))
    )
    (net (code "113") (name "unconnected-(LOW_POWER_OUTPUT--11-PadA11)") (class "Default")
      (node (ref "LOW_POWER_OUTPUT") (pin "A11") (pinfunction "-11_A11") (pintype "passive"))
    )
    (net (code "114") (name "unconnected-(LOW_POWER_OUTPUT--12-PadA12)") (class "Default")
      (node (ref "LOW_POWER_OUTPUT") (pin "A12") (pinfunction "-12_A12") (pintype "passive"))
    )
    (net (code "115") (name "unconnected-(PICKIT2-Pad6)") (class "Default")
      (node (ref "PICKIT2") (pin "6") (pinfunction "6_6") (pintype "passive"))
    )
    (net (code "116") (name "unconnected-(POWER--1-PadA1)") (class "Default")
      (node (ref "POWER") (pin "A1") (pinfunction "-1_A1") (pintype "passive"))
    )
    (net (code "117") (name "unconnected-(POWER--2-PadA2)") (class "Default")
      (node (ref "POWER") (pin "A2") (pinfunction "-2_A2") (pintype "passive"))
    )
    (net (code "118") (name "unconnected-(TRACK_STATUS--1-PadA1)") (class "Default")
      (node (ref "TRACK_STATUS") (pin "A1") (pinfunction "-1_A1") (pintype "passive"))
    )
    (net (code "119") (name "unconnected-(TRACK_STATUS--2-PadA2)") (class "Default")
      (node (ref "TRACK_STATUS") (pin "A2") (pinfunction "-2_A2") (pintype "passive"))
    )
    (net (code "120") (name "unconnected-(TRACK_STATUS--3-PadA3)") (class "Default")
      (node (ref "TRACK_STATUS") (pin "A3") (pinfunction "-3_A3") (pintype "passive"))
    )
    (net (code "121") (name "unconnected-(TRACK_STATUS--4-PadA4)") (class "Default")
      (node (ref "TRACK_STATUS") (pin "A4") (pinfunction "-4_A4") (pintype "passive"))
    )
    (net (code "122") (name "unconnected-(X1-Pad1)") (class "Default")
      (node (ref "X1") (pin "1") (pinfunction "1_1") (pintype "passive"))
    )
    (net (code "123") (name "unconnected-(X1-Pad9)") (class "Default")
      (node (ref "X1") (pin "9") (pinfunction "9_9") (pintype "passive"))
    )
  )
)
